# queso_dip_v4_2.net
KiCad netlist of a schematic drawn in EAGLE
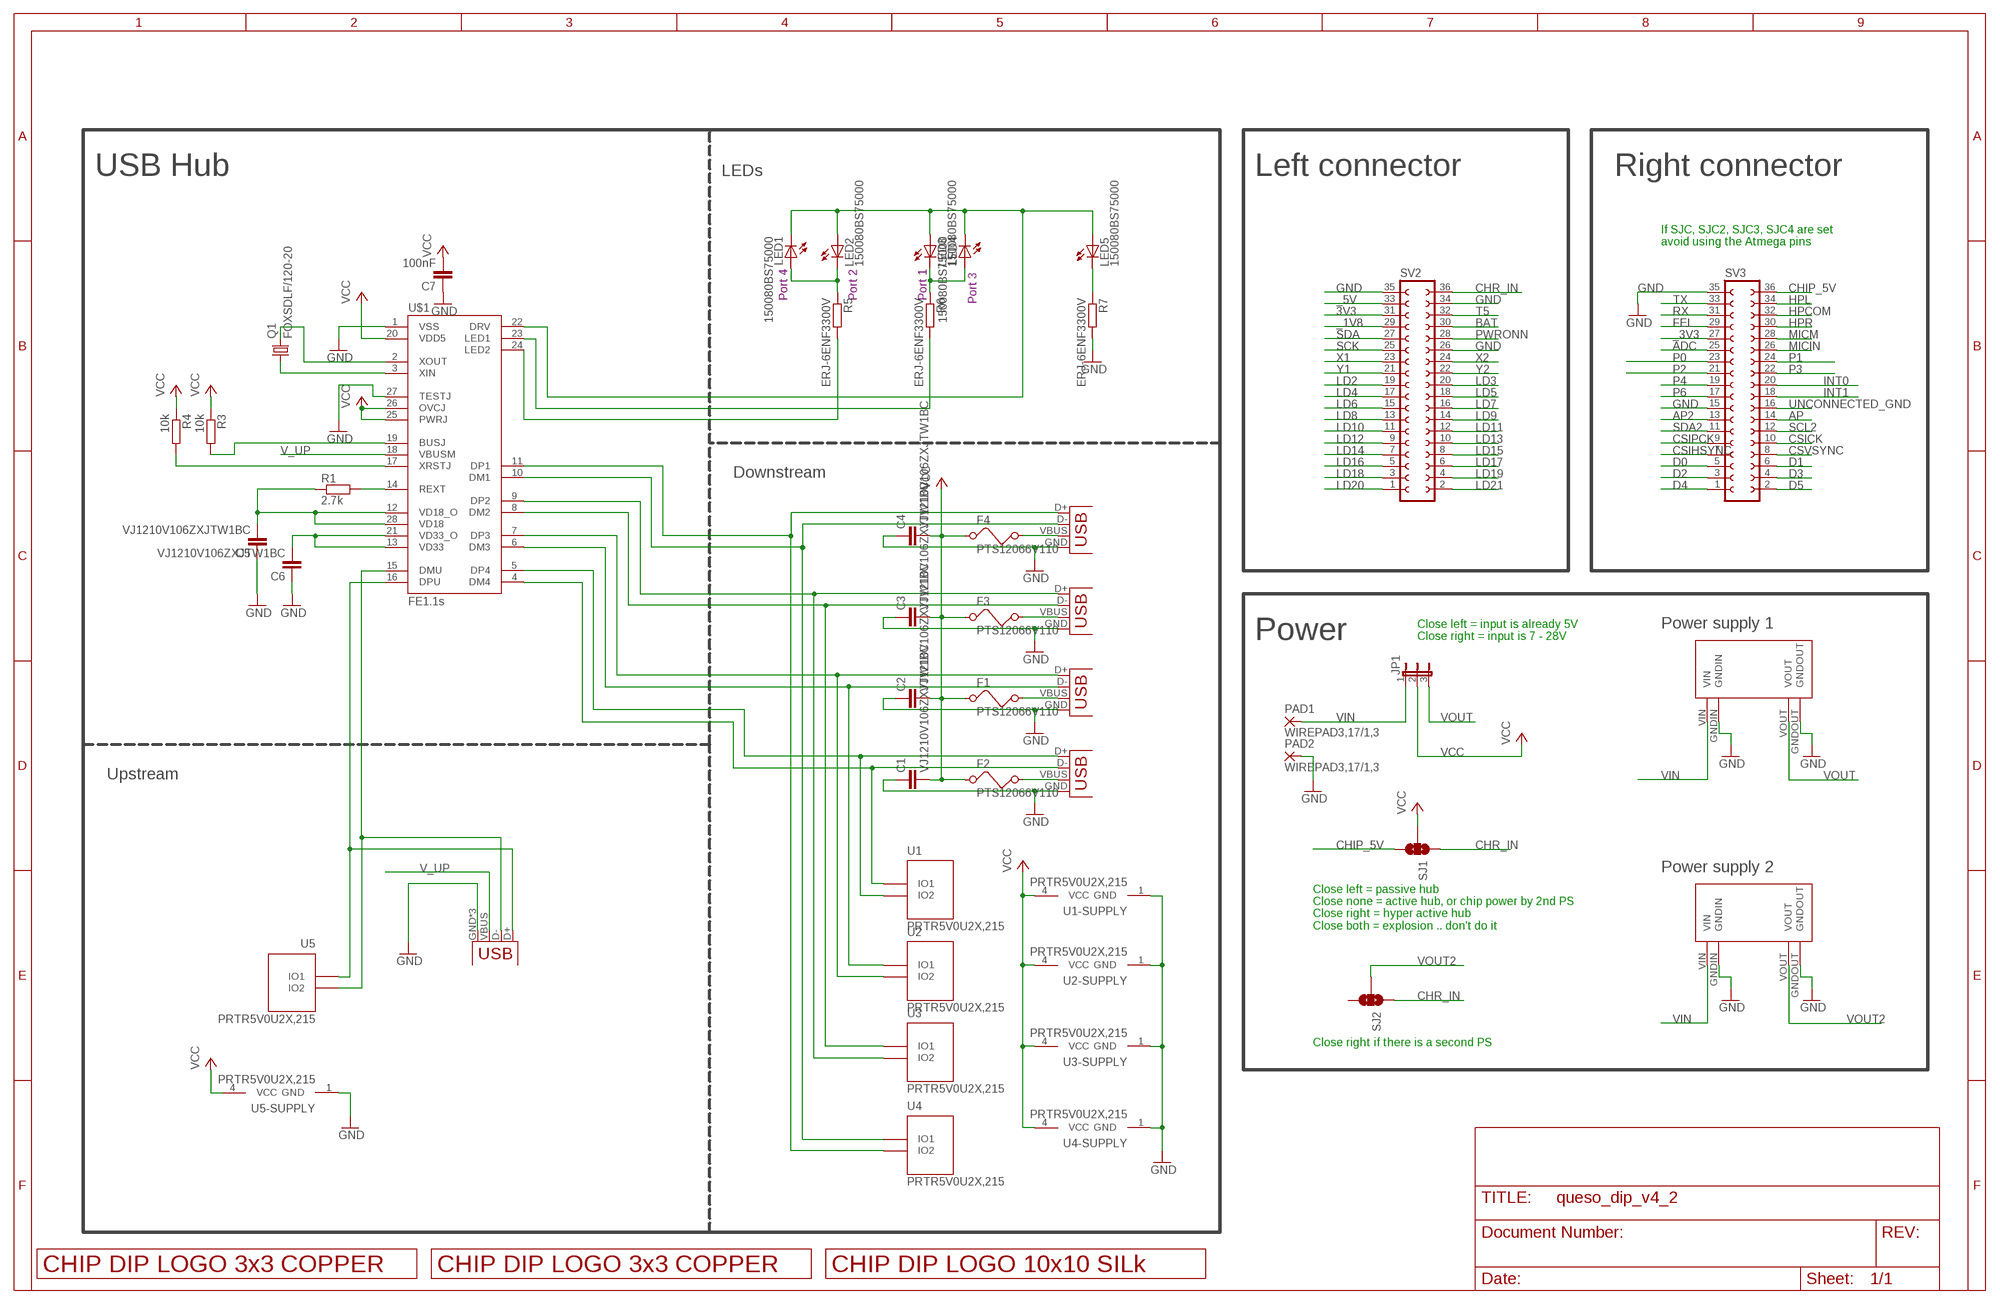
[diagram p0: schematic, sheet 1]

(export (version "E")
  (design (tool "Eeschema 10.0.6"))
  (components
    (comp (ref "C1")
      (value "VJ1210V106ZXJTW1BC")
      (footprint "eagle-import:C1210")
      (libsource (lib "eagle-import") (part "C-EUC1210"))
    )
    (comp (ref "C2")
      (value "VJ1210V106ZXJTW1BC")
      (footprint "eagle-import:C1210")
      (libsource (lib "eagle-import") (part "C-EUC1210"))
    )
    (comp (ref "C3")
      (value "VJ1210V106ZXJTW1BC")
      (footprint "eagle-import:C1210")
      (libsource (lib "eagle-import") (part "C-EUC1210"))
    )
    (comp (ref "C4")
      (value "VJ1210V106ZXJTW1BC")
      (footprint "eagle-import:C1210")
      (libsource (lib "eagle-import") (part "C-EUC1210"))
    )
    (comp (ref "C5")
      (value "VJ1210V106ZXJTW1BC")
      (footprint "eagle-import:C1210")
      (libsource (lib "eagle-import") (part "C-EUC1210"))
    )
    (comp (ref "C6")
      (value "VJ1210V106ZXJTW1BC")
      (footprint "eagle-import:C1210")
      (libsource (lib "eagle-import") (part "C-EUC1210"))
    )
    (comp (ref "C7")
      (value "100nF")
      (footprint "eagle-import:C0805")
      (libsource (lib "eagle-import") (part "C-EUC0805"))
    )
    (comp (ref "F1")
      (value "PTS12066V110")
      (footprint "eagle-import:1210")
      (libsource (lib "eagle-import") (part "FUSED"))
    )
    (comp (ref "F2")
      (value "PTS12066V110")
      (footprint "eagle-import:1210")
      (libsource (lib "eagle-import") (part "FUSED"))
    )
    (comp (ref "F3")
      (value "PTS12066V110")
      (footprint "eagle-import:1210")
      (libsource (lib "eagle-import") (part "FUSED"))
    )
    (comp (ref "F4")
      (value "PTS12066V110")
      (footprint "eagle-import:1210")
      (libsource (lib "eagle-import") (part "FUSED"))
    )
    (comp (ref "JP1")
      (value "JP2E")
      (footprint "eagle-import:JP2")
      (libsource (lib "eagle-import") (part "JP2E"))
    )
    (comp (ref "LED1")
      (value "150080BS75000")
      (footprint "eagle-import:CHIP-LED0805")
      (libsource (lib "eagle-import") (part "LEDCHIP-LED0805"))
    )
    (comp (ref "LED2")
      (value "150080BS75000")
      (footprint "eagle-import:CHIP-LED0805")
      (libsource (lib "eagle-import") (part "LEDCHIP-LED0805"))
    )
    (comp (ref "LED3")
      (value "150080BS75000")
      (footprint "eagle-import:CHIP-LED0805")
      (libsource (lib "eagle-import") (part "LEDCHIP-LED0805"))
    )
    (comp (ref "LED4")
      (value "150080BS75000")
      (footprint "eagle-import:CHIP-LED0805")
      (libsource (lib "eagle-import") (part "LEDCHIP-LED0805"))
    )
    (comp (ref "LED5")
      (value "150080BS75000")
      (footprint "eagle-import:CHIP-LED0805")
      (libsource (lib "eagle-import") (part "LEDCHIP-LED0805"))
    )
    (comp (ref "PAD1")
      (value "WIREPAD3,17/1,3")
      (footprint "eagle-import:3,17_1,3")
      (libsource (lib "eagle-import") (part "WIREPAD3,17/1,3"))
    )
    (comp (ref "PAD2")
      (value "WIREPAD3,17/1,3")
      (footprint "eagle-import:3,17_1,3")
      (libsource (lib "eagle-import") (part "WIREPAD3,17/1,3"))
    )
    (comp (ref "Q1")
      (value "FOXSDLF/120-20")
      (footprint "eagle-import:SM49")
      (libsource (lib "eagle-import") (part "CRYSTALSM49"))
    )
    (comp (ref "R1")
      (value "2.7k")
      (footprint "eagle-import:R0805")
      (libsource (lib "eagle-import") (part "R-EU_R0805"))
    )
    (comp (ref "R3")
      (value "10k")
      (footprint "eagle-import:R0805")
      (libsource (lib "eagle-import") (part "R-EU_R0805"))
    )
    (comp (ref "R4")
      (value "10k")
      (footprint "eagle-import:R0805")
      (libsource (lib "eagle-import") (part "R-EU_R0805"))
    )
    (comp (ref "R5")
      (value "ERJ-6ENF3300V")
      (footprint "eagle-import:R0805")
      (libsource (lib "eagle-import") (part "R-EU_R0805"))
    )
    (comp (ref "R6")
      (value "ERJ-6ENF3300V")
      (footprint "eagle-import:R0805")
      (libsource (lib "eagle-import") (part "R-EU_R0805"))
    )
    (comp (ref "R7")
      (value "ERJ-6ENF3300V")
      (footprint "eagle-import:R0805")
      (libsource (lib "eagle-import") (part "R-EU_R0805"))
    )
    (comp (ref "SJ1")
      (value "SOLDERJUMPER_2WAYT")
      (footprint "eagle-import:SJ_2")
      (libsource (lib "eagle-import") (part "SOLDERJUMPER_2WAYT"))
    )
    (comp (ref "SJ2")
      (value "SOLDERJUMPER_2WAYT")
      (footprint "eagle-import:SJ_2")
      (libsource (lib "eagle-import") (part "SOLDERJUMPER_2WAYT"))
    )
    (comp (ref "SV2")
      (value "FE18-2")
      (footprint "eagle-import:FE18-2")
      (libsource (lib "eagle-import") (part "FE18-2"))
    )
    (comp (ref "SV3")
      (value "FE18-2")
      (footprint "eagle-import:FE18-2")
      (libsource (lib "eagle-import") (part "FE18-2"))
    )
    (comp (ref "U$1")
      (value "FE1.1S")
      (footprint "eagle-import:FE1.1S_SSOP-28")
      (libsource (lib "eagle-import") (part "FE1.1S"))
    )
    (comp (ref "U$2")
      (value "LOGO_3X3_COPPER")
      (footprint "eagle-import:LOGO_3X3_COPPER")
      (libsource (lib "eagle-import") (part "LOGO_3X3_COPPER"))
    )
    (comp (ref "U$3")
      (value "MP1584EN")
      (footprint "eagle-import:MP1584EN")
      (libsource (lib "eagle-import") (part "MP1584EN"))
    )
    (comp (ref "U$4")
      (value "LOGO_3X3_COPPER")
      (footprint "eagle-import:LOGO_3X3_COPPER")
      (libsource (lib "eagle-import") (part "LOGO_3X3_COPPER"))
    )
    (comp (ref "U$5")
      (value "LOGO_10X10_SILK")
      (footprint "eagle-import:LOGO_10X10_SILK")
      (libsource (lib "eagle-import") (part "LOGO_10X10_SILK"))
    )
    (comp (ref "U$9")
      (value "MP1584EN")
      (footprint "eagle-import:MP1584EN")
      (libsource (lib "eagle-import") (part "MP1584EN"))
    )
    (comp (ref "U1")
      (value "PRTR5V0U2X,215")
      (footprint "eagle-import:SOT-143B")
      (fields (field (name "MANUFACTURER") "NXP Semiconductors"))
      (libsource (lib "eagle-import") (part "PRTR5V0U2X?"))
    )
    (comp (ref "U2")
      (value "PRTR5V0U2X,215")
      (footprint "eagle-import:SOT-143B")
      (fields (field (name "MANUFACTURER") "NXP Semiconductors"))
      (libsource (lib "eagle-import") (part "PRTR5V0U2X?"))
    )
    (comp (ref "U3")
      (value "PRTR5V0U2X,215")
      (footprint "eagle-import:SOT-143B")
      (fields (field (name "MANUFACTURER") "NXP Semiconductors"))
      (libsource (lib "eagle-import") (part "PRTR5V0U2X?"))
    )
    (comp (ref "U4")
      (value "PRTR5V0U2X,215")
      (footprint "eagle-import:SOT-143B")
      (fields (field (name "MANUFACTURER") "NXP Semiconductors"))
      (libsource (lib "eagle-import") (part "PRTR5V0U2X?"))
    )
    (comp (ref "U5")
      (value "PRTR5V0U2X,215")
      (footprint "eagle-import:SOT-143B")
      (fields (field (name "MANUFACTURER") "NXP Semiconductors"))
      (libsource (lib "eagle-import") (part "PRTR5V0U2X?"))
    )
    (comp (ref "USB")
      (value "USBUSB-MICROB-SMT-DIP")
      (footprint "eagle-import:USB-MICROB-SMT-DIP")
      (libsource (lib "eagle-import") (part "USBUSB-MICROB-SMT-DIP"))
    )
    (comp (ref "X1")
      (value "USB-A-HU")
      (footprint "eagle-import:USB-A-HU")
      (libsource (lib "eagle-import") (part "USB-A-HU"))
    )
    (comp (ref "X2")
      (value "USB-A-HU")
      (footprint "eagle-import:USB-A-HU")
      (libsource (lib "eagle-import") (part "USB-A-HU"))
    )
    (comp (ref "X3")
      (value "USB-A-HU")
      (footprint "eagle-import:USB-A-HU")
      (libsource (lib "eagle-import") (part "USB-A-HU"))
    )
    (comp (ref "X4")
      (value "USB-A-HU")
      (footprint "eagle-import:USB-A-HU")
      (libsource (lib "eagle-import") (part "USB-A-HU"))
    )
  )
  (nets
    (net (code "1") (name "/3V3") (class "Default")
      (node (ref "SV2") (pin "31") (pinfunction "31_31") (pintype "passive"))
    )
    (net (code "2") (name "/ADC") (class "Default")
      (node (ref "SV3") (pin "25") (pinfunction "25_25") (pintype "passive"))
    )
    (net (code "3") (name "/AP") (class "Default")
      (node (ref "SV3") (pin "14") (pinfunction "14_14") (pintype "passive"))
    )
    (net (code "4") (name "/AP2") (class "Default")
      (node (ref "SV3") (pin "13") (pinfunction "13_13") (pintype "passive"))
    )
    (net (code "5") (name "/BAT") (class "Default")
      (node (ref "SV2") (pin "30") (pinfunction "30_30") (pintype "passive"))
    )
    (net (code "6") (name "/CHIP_5V") (class "Default")
      (node (ref "SJ1") (pin "3") (pinfunction "3_3") (pintype "passive"))
      (node (ref "SV3") (pin "36") (pinfunction "36_36") (pintype "passive"))
    )
    (net (code "7") (name "/CHR_IN") (class "Default")
      (node (ref "SJ1") (pin "1") (pinfunction "1_1") (pintype "passive"))
      (node (ref "SJ2") (pin "1") (pinfunction "1_1") (pintype "passive"))
      (node (ref "SV2") (pin "36") (pinfunction "36_36") (pintype "passive"))
    )
    (net (code "8") (name "/CSICK") (class "Default")
      (node (ref "SV3") (pin "10") (pinfunction "10_10") (pintype "passive"))
    )
    (net (code "9") (name "/CSIHSYNC") (class "Default")
      (node (ref "SV3") (pin "7") (pinfunction "7_7") (pintype "passive"))
    )
    (net (code "10") (name "/CSIPCK") (class "Default")
      (node (ref "SV3") (pin "9") (pinfunction "9_9") (pintype "passive"))
    )
    (net (code "11") (name "/CSVSYNC") (class "Default")
      (node (ref "SV3") (pin "8") (pinfunction "8_8") (pintype "passive"))
    )
    (net (code "12") (name "/D0") (class "Default")
      (node (ref "SV3") (pin "5") (pinfunction "5_5") (pintype "passive"))
    )
    (net (code "13") (name "/D1") (class "Default")
      (node (ref "SV3") (pin "6") (pinfunction "6_6") (pintype "passive"))
    )
    (net (code "14") (name "/D2") (class "Default")
      (node (ref "SV3") (pin "3") (pinfunction "3_3") (pintype "passive"))
    )
    (net (code "15") (name "/D3") (class "Default")
      (node (ref "SV3") (pin "4") (pinfunction "4_4") (pintype "passive"))
    )
    (net (code "16") (name "/D4") (class "Default")
      (node (ref "SV3") (pin "1") (pinfunction "1_1") (pintype "passive"))
    )
    (net (code "17") (name "/D5") (class "Default")
      (node (ref "SV3") (pin "2") (pinfunction "2_2") (pintype "passive"))
    )
    (net (code "18") (name "/FEL") (class "Default")
      (node (ref "SV3") (pin "29") (pinfunction "29_29") (pintype "passive"))
    )
    (net (code "19") (name "/HPCOM") (class "Default")
      (node (ref "SV3") (pin "32") (pinfunction "32_32") (pintype "passive"))
    )
    (net (code "20") (name "/HPL") (class "Default")
      (node (ref "SV3") (pin "34") (pinfunction "34_34") (pintype "passive"))
    )
    (net (code "21") (name "/HPR") (class "Default")
      (node (ref "SV3") (pin "30") (pinfunction "30_30") (pintype "passive"))
    )
    (net (code "22") (name "/INT0") (class "Default")
      (node (ref "SV3") (pin "20") (pinfunction "20_20") (pintype "passive"))
    )
    (net (code "23") (name "/INT1") (class "Default")
      (node (ref "SV3") (pin "18") (pinfunction "18_18") (pintype "passive"))
    )
    (net (code "24") (name "/LD2") (class "Default")
      (node (ref "SV2") (pin "19") (pinfunction "19_19") (pintype "passive"))
    )
    (net (code "25") (name "/LD3") (class "Default")
      (node (ref "SV2") (pin "20") (pinfunction "20_20") (pintype "passive"))
    )
    (net (code "26") (name "/LD4") (class "Default")
      (node (ref "SV2") (pin "17") (pinfunction "17_17") (pintype "passive"))
    )
    (net (code "27") (name "/LD5") (class "Default")
      (node (ref "SV2") (pin "18") (pinfunction "18_18") (pintype "passive"))
    )
    (net (code "28") (name "/LD6") (class "Default")
      (node (ref "SV2") (pin "15") (pinfunction "15_15") (pintype "passive"))
    )
    (net (code "29") (name "/LD7") (class "Default")
      (node (ref "SV2") (pin "16") (pinfunction "16_16") (pintype "passive"))
    )
    (net (code "30") (name "/LD8") (class "Default")
      (node (ref "SV2") (pin "13") (pinfunction "13_13") (pintype "passive"))
    )
    (net (code "31") (name "/LD9") (class "Default")
      (node (ref "SV2") (pin "14") (pinfunction "14_14") (pintype "passive"))
    )
    (net (code "32") (name "/LD10") (class "Default")
      (node (ref "SV2") (pin "11") (pinfunction "11_11") (pintype "passive"))
    )
    (net (code "33") (name "/LD11") (class "Default")
      (node (ref "SV2") (pin "12") (pinfunction "12_12") (pintype "passive"))
    )
    (net (code "34") (name "/LD12") (class "Default")
      (node (ref "SV2") (pin "9") (pinfunction "9_9") (pintype "passive"))
    )
    (net (code "35") (name "/LD13") (class "Default")
      (node (ref "SV2") (pin "10") (pinfunction "10_10") (pintype "passive"))
    )
    (net (code "36") (name "/LD14") (class "Default")
      (node (ref "SV2") (pin "7") (pinfunction "7_7") (pintype "passive"))
    )
    (net (code "37") (name "/LD15") (class "Default")
      (node (ref "SV2") (pin "8") (pinfunction "8_8") (pintype "passive"))
    )
    (net (code "38") (name "/LD16") (class "Default")
      (node (ref "SV2") (pin "5") (pinfunction "5_5") (pintype "passive"))
    )
    (net (code "39") (name "/LD17") (class "Default")
      (node (ref "SV2") (pin "6") (pinfunction "6_6") (pintype "passive"))
    )
    (net (code "40") (name "/LD18") (class "Default")
      (node (ref "SV2") (pin "3") (pinfunction "3_3") (pintype "passive"))
    )
    (net (code "41") (name "/LD19") (class "Default")
      (node (ref "SV2") (pin "4") (pinfunction "4_4") (pintype "passive"))
    )
    (net (code "42") (name "/LD20") (class "Default")
      (node (ref "SV2") (pin "1") (pinfunction "1_1") (pintype "passive"))
    )
    (net (code "43") (name "/LD21") (class "Default")
      (node (ref "SV2") (pin "2") (pinfunction "2_2") (pintype "passive"))
    )
    (net (code "44") (name "/MICIN") (class "Default")
      (node (ref "SV3") (pin "26") (pinfunction "26_26") (pintype "passive"))
    )
    (net (code "45") (name "/MICM") (class "Default")
      (node (ref "SV3") (pin "28") (pinfunction "28_28") (pintype "passive"))
    )
    (net (code "46") (name "/P0") (class "Default")
      (node (ref "SV3") (pin "23") (pinfunction "23_23") (pintype "passive"))
    )
    (net (code "47") (name "/P1") (class "Default")
      (node (ref "SV3") (pin "24") (pinfunction "24_24") (pintype "passive"))
    )
    (net (code "48") (name "/P2") (class "Default")
      (node (ref "SV3") (pin "21") (pinfunction "21_21") (pintype "passive"))
    )
    (net (code "49") (name "/P3") (class "Default")
      (node (ref "SV3") (pin "22") (pinfunction "22_22") (pintype "passive"))
    )
    (net (code "50") (name "/P4") (class "Default")
      (node (ref "SV3") (pin "19") (pinfunction "19_19") (pintype "passive"))
    )
    (net (code "51") (name "/P6") (class "Default")
      (node (ref "SV3") (pin "17") (pinfunction "17_17") (pintype "passive"))
    )
    (net (code "52") (name "/PWRONN") (class "Default")
      (node (ref "SV2") (pin "28") (pinfunction "28_28") (pintype "passive"))
    )
    (net (code "53") (name "/RX") (class "Default")
      (node (ref "SV3") (pin "31") (pinfunction "31_31") (pintype "passive"))
    )
    (net (code "54") (name "/SCK") (class "Default")
      (node (ref "SV2") (pin "25") (pinfunction "25_25") (pintype "passive"))
    )
    (net (code "55") (name "/SCL2") (class "Default")
      (node (ref "SV3") (pin "12") (pinfunction "12_12") (pintype "passive"))
    )
    (net (code "56") (name "/SDA") (class "Default")
      (node (ref "SV2") (pin "27") (pinfunction "27_27") (pintype "passive"))
    )
    (net (code "57") (name "/SDA2") (class "Default")
      (node (ref "SV3") (pin "11") (pinfunction "11_11") (pintype "passive"))
    )
    (net (code "58") (name "/T5") (class "Default")
      (node (ref "SV2") (pin "32") (pinfunction "32_32") (pintype "passive"))
    )
    (net (code "59") (name "/TX") (class "Default")
      (node (ref "SV3") (pin "33") (pinfunction "33_33") (pintype "passive"))
    )
    (net (code "60") (name "/UNCONNECTED_GND") (class "Default")
      (node (ref "SV3") (pin "16") (pinfunction "16_16") (pintype "passive"))
    )
    (net (code "61") (name "/VIN") (class "Default")
      (node (ref "JP1") (pin "1") (pinfunction "1_1") (pintype "passive"))
      (node (ref "PAD1") (pin "1") (pinfunction "P_1") (pintype "passive"))
      (node (ref "U$3") (pin "VIN") (pinfunction "VIN_VIN") (pintype "power_in"))
      (node (ref "U$9") (pin "VIN") (pinfunction "VIN_VIN") (pintype "power_in"))
    )
    (net (code "62") (name "/VOUT") (class "Default")
      (node (ref "JP1") (pin "3") (pinfunction "3_3") (pintype "passive"))
      (node (ref "U$9") (pin "VOUT") (pinfunction "VOUT_VOUT") (pintype "power_in"))
    )
    (net (code "63") (name "/VOUT2") (class "Default")
      (node (ref "SJ2") (pin "2") (pinfunction "2_2") (pintype "passive"))
      (node (ref "U$3") (pin "VOUT") (pinfunction "VOUT_VOUT") (pintype "power_in"))
    )
    (net (code "64") (name "/V_UP") (class "Default")
      (node (ref "U$1") (pin "18") (pinfunction "VBUSM_18") (pintype "bidirectional"))
      (node (ref "USB") (pin "VBUS") (pinfunction "VBUS_VBUS") (pintype "bidirectional"))
    )
    (net (code "65") (name "/X1") (class "Default")
      (node (ref "SV2") (pin "23") (pinfunction "23_23") (pintype "passive"))
    )
    (net (code "66") (name "/X2") (class "Default")
      (node (ref "SV2") (pin "24") (pinfunction "24_24") (pintype "passive"))
    )
    (net (code "67") (name "/Y1") (class "Default")
      (node (ref "SV2") (pin "21") (pinfunction "21_21") (pintype "passive"))
    )
    (net (code "68") (name "/Y2") (class "Default")
      (node (ref "SV2") (pin "22") (pinfunction "22_22") (pintype "passive"))
    )
    (net (code "69") (name "/_1V8") (class "Default")
      (node (ref "SV2") (pin "29") (pinfunction "29_29") (pintype "passive"))
    )
    (net (code "70") (name "/_3V3") (class "Default")
      (node (ref "SV3") (pin "27") (pinfunction "27_27") (pintype "passive"))
    )
    (net (code "71") (name "/_5V") (class "Default")
      (node (ref "SV2") (pin "33") (pinfunction "33_33") (pintype "passive"))
    )
    (net (code "72") (name "GND") (class "Default")
      (node (ref "C1") (pin "1") (pinfunction "1_1") (pintype "passive"))
      (node (ref "C2") (pin "1") (pinfunction "1_1") (pintype "passive"))
      (node (ref "C3") (pin "1") (pinfunction "1_1") (pintype "passive"))
      (node (ref "C4") (pin "1") (pinfunction "1_1") (pintype "passive"))
      (node (ref "C5") (pin "1") (pinfunction "1_1") (pintype "passive"))
      (node (ref "C6") (pin "1") (pinfunction "1_1") (pintype "passive"))
      (node (ref "C7") (pin "1") (pinfunction "1_1") (pintype "passive"))
      (node (ref "PAD2") (pin "1") (pinfunction "P_1") (pintype "passive"))
      (node (ref "R7") (pin "2") (pinfunction "2_2") (pintype "passive"))
      (node (ref "SV2") (pin "26") (pinfunction "26_26") (pintype "passive"))
      (node (ref "SV2") (pin "34") (pinfunction "34_34") (pintype "passive"))
      (node (ref "SV2") (pin "35") (pinfunction "35_35") (pintype "passive"))
      (node (ref "SV3") (pin "15") (pinfunction "15_15") (pintype "passive"))
      (node (ref "SV3") (pin "35") (pinfunction "35_35") (pintype "passive"))
      (node (ref "U$1") (pin "1") (pinfunction "VSS_1") (pintype "bidirectional"))
      (node (ref "U$1") (pin "27") (pinfunction "TESTJ_27") (pintype "bidirectional"))
      (node (ref "U$3") (pin "GNDIN") (pinfunction "GNDIN_GNDIN") (pintype "power_in"))
      (node (ref "U$3") (pin "GNDOUT") (pinfunction "GNDOUT_GNDOUT") (pintype "power_in"))
      (node (ref "U$9") (pin "GNDIN") (pinfunction "GNDIN_GNDIN") (pintype "power_in"))
      (node (ref "U$9") (pin "GNDOUT") (pinfunction "GNDOUT_GNDOUT") (pintype "power_in"))
      (node (ref "U1") (pin "1") (pinfunction "GND_1") (pintype "bidirectional"))
      (node (ref "U2") (pin "1") (pinfunction "GND_1") (pintype "bidirectional"))
      (node (ref "U3") (pin "1") (pinfunction "GND_1") (pintype "bidirectional"))
      (node (ref "U4") (pin "1") (pinfunction "GND_1") (pintype "bidirectional"))
      (node (ref "U5") (pin "1") (pinfunction "GND_1") (pintype "bidirectional"))
      (node (ref "USB") (pin "GND") (pinfunction "GND_GND") (pintype "bidirectional"))
      (node (ref "USB") (pin "MT1") (pinfunction "GND_MT1") (pintype "bidirectional"))
      (node (ref "USB") (pin "MT2") (pinfunction "GND_MT2") (pintype "bidirectional"))
      (node (ref "X1") (pin "GND") (pinfunction "GND_GND") (pintype "bidirectional"))
      (node (ref "X2") (pin "GND") (pinfunction "GND_GND") (pintype "bidirectional"))
      (node (ref "X3") (pin "GND") (pinfunction "GND_GND") (pintype "bidirectional"))
      (node (ref "X4") (pin "GND") (pinfunction "GND_GND") (pintype "bidirectional"))
    )
    (net (code "73") (name "Net-(F1-Pad2)") (class "Default")
      (node (ref "F1") (pin "2") (pinfunction "2_2") (pintype "passive"))
      (node (ref "X2") (pin "VBUS") (pinfunction "VBUS_VBUS") (pintype "bidirectional"))
    )
    (net (code "74") (name "Net-(F2-Pad2)") (class "Default")
      (node (ref "F2") (pin "2") (pinfunction "2_2") (pintype "passive"))
      (node (ref "X1") (pin "VBUS") (pinfunction "VBUS_VBUS") (pintype "bidirectional"))
    )
    (net (code "75") (name "Net-(F3-Pad2)") (class "Default")
      (node (ref "F3") (pin "2") (pinfunction "2_2") (pintype "passive"))
      (node (ref "X3") (pin "VBUS") (pinfunction "VBUS_VBUS") (pintype "bidirectional"))
    )
    (net (code "76") (name "Net-(F4-Pad2)") (class "Default")
      (node (ref "F4") (pin "2") (pinfunction "2_2") (pintype "passive"))
      (node (ref "X4") (pin "VBUS") (pinfunction "VBUS_VBUS") (pintype "bidirectional"))
    )
    (net (code "77") (name "Net-(LED1-PadA)") (class "Default")
      (node (ref "LED1") (pin "A") (pinfunction "A_A") (pintype "passive"))
      (node (ref "LED2") (pin "C") (pinfunction "C_C") (pintype "passive"))
      (node (ref "R5") (pin "1") (pinfunction "1_1") (pintype "passive"))
    )
    (net (code "78") (name "Net-(LED3-PadC)") (class "Default")
      (node (ref "LED3") (pin "C") (pinfunction "C_C") (pintype "passive"))
      (node (ref "LED4") (pin "A") (pinfunction "A_A") (pintype "passive"))
      (node (ref "R6") (pin "1") (pinfunction "1_1") (pintype "passive"))
    )
    (net (code "79") (name "Net-(LED5-PadC)") (class "Default")
      (node (ref "LED5") (pin "C") (pinfunction "C_C") (pintype "passive"))
      (node (ref "R7") (pin "1") (pinfunction "1_1") (pintype "passive"))
    )
    (net (code "80") (name "Net-(U$1-BUSJ)") (class "Default")
      (node (ref "R3") (pin "2") (pinfunction "2_2") (pintype "passive"))
      (node (ref "U$1") (pin "19") (pinfunction "BUSJ_19") (pintype "bidirectional"))
    )
    (net (code "81") (name "Net-(U$1-DM1)") (class "Default")
      (node (ref "U$1") (pin "10") (pinfunction "DM1_10") (pintype "bidirectional"))
      (node (ref "U4") (pin "2") (pinfunction "IO1_2") (pintype "bidirectional"))
      (node (ref "X4") (pin "D-") (pinfunction "D-_D-") (pintype "bidirectional"))
    )
    (net (code "82") (name "Net-(U$1-DM2)") (class "Default")
      (node (ref "U$1") (pin "8") (pinfunction "DM2_8") (pintype "bidirectional"))
      (node (ref "U3") (pin "2") (pinfunction "IO1_2") (pintype "bidirectional"))
      (node (ref "X3") (pin "D-") (pinfunction "D-_D-") (pintype "bidirectional"))
    )
    (net (code "83") (name "Net-(U$1-DM3)") (class "Default")
      (node (ref "U$1") (pin "6") (pinfunction "DM3_6") (pintype "bidirectional"))
      (node (ref "U2") (pin "2") (pinfunction "IO1_2") (pintype "bidirectional"))
      (node (ref "X2") (pin "D-") (pinfunction "D-_D-") (pintype "bidirectional"))
    )
    (net (code "84") (name "Net-(U$1-DM4)") (class "Default")
      (node (ref "U$1") (pin "4") (pinfunction "DM4_4") (pintype "bidirectional"))
      (node (ref "U1") (pin "2") (pinfunction "IO1_2") (pintype "bidirectional"))
      (node (ref "X1") (pin "D-") (pinfunction "D-_D-") (pintype "bidirectional"))
    )
    (net (code "85") (name "Net-(U$1-DMU)") (class "Default")
      (node (ref "U$1") (pin "15") (pinfunction "DMU_15") (pintype "bidirectional"))
      (node (ref "U5") (pin "3") (pinfunction "IO2_3") (pintype "bidirectional"))
      (node (ref "USB") (pin "D-") (pinfunction "D-_D-") (pintype "bidirectional"))
    )
    (net (code "86") (name "Net-(U$1-DP1)") (class "Default")
      (node (ref "U$1") (pin "11") (pinfunction "DP1_11") (pintype "bidirectional"))
      (node (ref "U4") (pin "3") (pinfunction "IO2_3") (pintype "bidirectional"))
      (node (ref "X4") (pin "D+") (pinfunction "D+_D+") (pintype "bidirectional"))
    )
    (net (code "87") (name "Net-(U$1-DP2)") (class "Default")
      (node (ref "U$1") (pin "9") (pinfunction "DP2_9") (pintype "bidirectional"))
      (node (ref "U3") (pin "3") (pinfunction "IO2_3") (pintype "bidirectional"))
      (node (ref "X3") (pin "D+") (pinfunction "D+_D+") (pintype "bidirectional"))
    )
    (net (code "88") (name "Net-(U$1-DP3)") (class "Default")
      (node (ref "U$1") (pin "7") (pinfunction "DP3_7") (pintype "bidirectional"))
      (node (ref "U2") (pin "3") (pinfunction "IO2_3") (pintype "bidirectional"))
      (node (ref "X2") (pin "D+") (pinfunction "D+_D+") (pintype "bidirectional"))
    )
    (net (code "89") (name "Net-(U$1-DP4)") (class "Default")
      (node (ref "U$1") (pin "5") (pinfunction "DP4_5") (pintype "bidirectional"))
      (node (ref "U1") (pin "3") (pinfunction "IO2_3") (pintype "bidirectional"))
      (node (ref "X1") (pin "D+") (pinfunction "D+_D+") (pintype "bidirectional"))
    )
    (net (code "90") (name "Net-(U$1-DPU)") (class "Default")
      (node (ref "U$1") (pin "16") (pinfunction "DPU_16") (pintype "bidirectional"))
      (node (ref "U5") (pin "2") (pinfunction "IO1_2") (pintype "bidirectional"))
      (node (ref "USB") (pin "D+") (pinfunction "D+_D+") (pintype "bidirectional"))
    )
    (net (code "91") (name "Net-(U$1-DRV)") (class "Default")
      (node (ref "LED1") (pin "C") (pinfunction "C_C") (pintype "passive"))
      (node (ref "LED2") (pin "A") (pinfunction "A_A") (pintype "passive"))
      (node (ref "LED3") (pin "A") (pinfunction "A_A") (pintype "passive"))
      (node (ref "LED4") (pin "C") (pinfunction "C_C") (pintype "passive"))
      (node (ref "LED5") (pin "A") (pinfunction "A_A") (pintype "passive"))
      (node (ref "U$1") (pin "22") (pinfunction "DRV_22") (pintype "bidirectional"))
    )
    (net (code "92") (name "Net-(U$1-LED1)") (class "Default")
      (node (ref "R6") (pin "2") (pinfunction "2_2") (pintype "passive"))
      (node (ref "U$1") (pin "23") (pinfunction "LED1_23") (pintype "bidirectional"))
    )
    (net (code "93") (name "Net-(U$1-LED2)") (class "Default")
      (node (ref "R5") (pin "2") (pinfunction "2_2") (pintype "passive"))
      (node (ref "U$1") (pin "24") (pinfunction "LED2_24") (pintype "bidirectional"))
    )
    (net (code "94") (name "Net-(U$1-REXT)") (class "Default")
      (node (ref "R1") (pin "2") (pinfunction "2_2") (pintype "passive"))
      (node (ref "U$1") (pin "14") (pinfunction "REXT_14") (pintype "bidirectional"))
    )
    (net (code "95") (name "Net-(U$1-VD18)") (class "Default")
      (node (ref "C5") (pin "2") (pinfunction "2_2") (pintype "passive"))
      (node (ref "R1") (pin "1") (pinfunction "1_1") (pintype "passive"))
      (node (ref "U$1") (pin "12") (pinfunction "VD18_O_12") (pintype "bidirectional"))
      (node (ref "U$1") (pin "28") (pinfunction "VD18_28") (pintype "bidirectional"))
    )
    (net (code "96") (name "Net-(U$1-VD33)") (class "Default")
      (node (ref "C6") (pin "2") (pinfunction "2_2") (pintype "passive"))
      (node (ref "U$1") (pin "13") (pinfunction "VD33_13") (pintype "bidirectional"))
      (node (ref "U$1") (pin "21") (pinfunction "VD33_O_21") (pintype "bidirectional"))
    )
    (net (code "97") (name "Net-(U$1-XIN)") (class "Default")
      (node (ref "Q1") (pin "1") (pinfunction "1_1") (pintype "passive"))
      (node (ref "U$1") (pin "3") (pinfunction "XIN_3") (pintype "bidirectional"))
    )
    (net (code "98") (name "Net-(U$1-XOUT)") (class "Default")
      (node (ref "Q1") (pin "2") (pinfunction "2_2") (pintype "passive"))
      (node (ref "U$1") (pin "2") (pinfunction "XOUT_2") (pintype "bidirectional"))
    )
    (net (code "99") (name "Net-(U$1-XRSTJ)") (class "Default")
      (node (ref "R4") (pin "2") (pinfunction "2_2") (pintype "passive"))
      (node (ref "U$1") (pin "17") (pinfunction "XRSTJ_17") (pintype "bidirectional"))
    )
    (net (code "100") (name "VCC") (class "Default")
      (node (ref "C1") (pin "2") (pinfunction "2_2") (pintype "passive"))
      (node (ref "C2") (pin "2") (pinfunction "2_2") (pintype "passive"))
      (node (ref "C3") (pin "2") (pinfunction "2_2") (pintype "passive"))
      (node (ref "C4") (pin "2") (pinfunction "2_2") (pintype "passive"))
      (node (ref "C7") (pin "2") (pinfunction "2_2") (pintype "passive"))
      (node (ref "F1") (pin "1") (pinfunction "1_1") (pintype "passive"))
      (node (ref "F2") (pin "1") (pinfunction "1_1") (pintype "passive"))
      (node (ref "F3") (pin "1") (pinfunction "1_1") (pintype "passive"))
      (node (ref "F4") (pin "1") (pinfunction "1_1") (pintype "passive"))
      (node (ref "JP1") (pin "2") (pinfunction "2_2") (pintype "passive"))
      (node (ref "R3") (pin "1") (pinfunction "1_1") (pintype "passive"))
      (node (ref "R4") (pin "1") (pinfunction "1_1") (pintype "passive"))
      (node (ref "SJ1") (pin "2") (pinfunction "2_2") (pintype "passive"))
      (node (ref "U$1") (pin "20") (pinfunction "VDD5_20") (pintype "bidirectional"))
      (node (ref "U$1") (pin "25") (pinfunction "PWRJ_25") (pintype "bidirectional"))
      (node (ref "U$1") (pin "26") (pinfunction "OVCJ_26") (pintype "bidirectional"))
      (node (ref "U1") (pin "4") (pinfunction "VCC_4") (pintype "bidirectional"))
      (node (ref "U2") (pin "4") (pinfunction "VCC_4") (pintype "bidirectional"))
      (node (ref "U3") (pin "4") (pinfunction "VCC_4") (pintype "bidirectional"))
      (node (ref "U4") (pin "4") (pinfunction "VCC_4") (pintype "bidirectional"))
      (node (ref "U5") (pin "4") (pinfunction "VCC_4") (pintype "bidirectional"))
    )
    (net (code "101") (name "unconnected-(SJ2-Pad3)") (class "Default")
      (node (ref "SJ2") (pin "3") (pinfunction "3_3") (pintype "passive"))
    )
  )
)
